# W050X.net
KiCad netlist of a schematic drawn in EAGLE
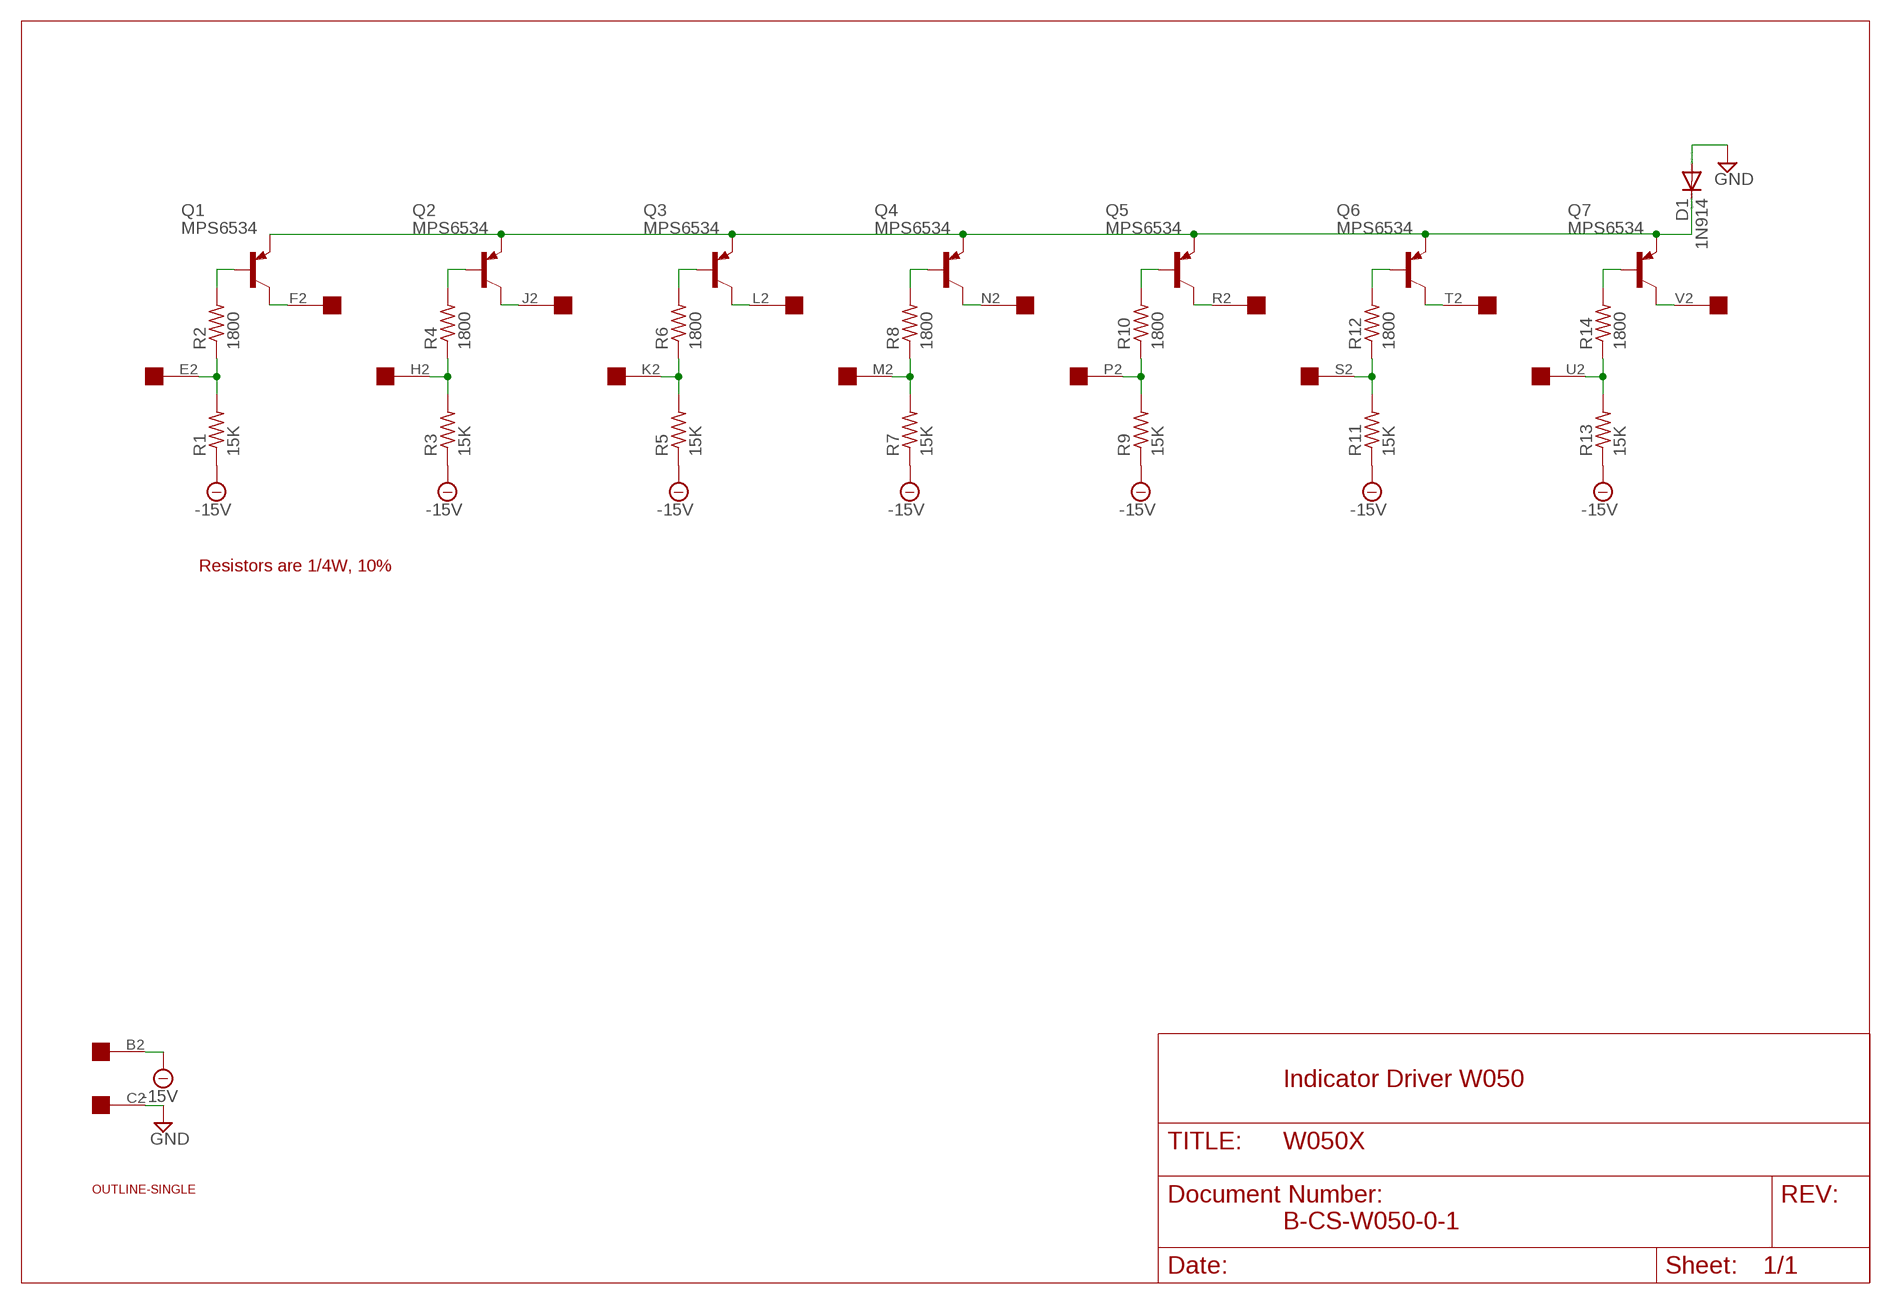
[diagram p0: schematic, sheet 1]

(export (version "E")
  (design (tool "Eeschema 10.0.6"))
  (components
    (comp (ref "D1")
      (value "1N914")
      (footprint "eagle-import:DO35-10")
      (libsource (lib "eagle-import") (part "1N4148DO35-10"))
    )
    (comp (ref "EDGE")
      (value "EDGE-1")
      (footprint "eagle-import:EDGE-CON1")
      (libsource (lib "eagle-import") (part "EDGE-1"))
    )
    (comp (ref "Q1")
      (value "MPS6534")
      (footprint "eagle-import:TO39")
      (libsource (lib "eagle-import") (part "2N2904"))
    )
    (comp (ref "Q2")
      (value "MPS6534")
      (footprint "eagle-import:TO39")
      (libsource (lib "eagle-import") (part "2N2904"))
    )
    (comp (ref "Q3")
      (value "MPS6534")
      (footprint "eagle-import:TO39")
      (libsource (lib "eagle-import") (part "2N2904"))
    )
    (comp (ref "Q4")
      (value "MPS6534")
      (footprint "eagle-import:TO39")
      (libsource (lib "eagle-import") (part "2N2904"))
    )
    (comp (ref "Q5")
      (value "MPS6534")
      (footprint "eagle-import:TO39")
      (libsource (lib "eagle-import") (part "2N2904"))
    )
    (comp (ref "Q6")
      (value "MPS6534")
      (footprint "eagle-import:TO39")
      (libsource (lib "eagle-import") (part "2N2904"))
    )
    (comp (ref "Q7")
      (value "MPS6534")
      (footprint "eagle-import:TO39")
      (libsource (lib "eagle-import") (part "2N2904"))
    )
    (comp (ref "R1")
      (value "15K")
      (footprint "eagle-import:0207_10")
      (libsource (lib "eagle-import") (part "R-US_0207/10"))
    )
    (comp (ref "R2")
      (value "1800")
      (footprint "eagle-import:0207_10")
      (libsource (lib "eagle-import") (part "R-US_0207/10"))
    )
    (comp (ref "R3")
      (value "15K")
      (footprint "eagle-import:0207_10")
      (libsource (lib "eagle-import") (part "R-US_0207/10"))
    )
    (comp (ref "R4")
      (value "1800")
      (footprint "eagle-import:0207_10")
      (libsource (lib "eagle-import") (part "R-US_0207/10"))
    )
    (comp (ref "R5")
      (value "15K")
      (footprint "eagle-import:0207_10")
      (libsource (lib "eagle-import") (part "R-US_0207/10"))
    )
    (comp (ref "R6")
      (value "1800")
      (footprint "eagle-import:0207_10")
      (libsource (lib "eagle-import") (part "R-US_0207/10"))
    )
    (comp (ref "R7")
      (value "15K")
      (footprint "eagle-import:0207_10")
      (libsource (lib "eagle-import") (part "R-US_0207/10"))
    )
    (comp (ref "R8")
      (value "1800")
      (footprint "eagle-import:0207_10")
      (libsource (lib "eagle-import") (part "R-US_0207/10"))
    )
    (comp (ref "R9")
      (value "15K")
      (footprint "eagle-import:0207_10")
      (libsource (lib "eagle-import") (part "R-US_0207/10"))
    )
    (comp (ref "R10")
      (value "1800")
      (footprint "eagle-import:0207_10")
      (libsource (lib "eagle-import") (part "R-US_0207/10"))
    )
    (comp (ref "R11")
      (value "15K")
      (footprint "eagle-import:0207_10")
      (libsource (lib "eagle-import") (part "R-US_0207/10"))
    )
    (comp (ref "R12")
      (value "1800")
      (footprint "eagle-import:0207_10")
      (libsource (lib "eagle-import") (part "R-US_0207/10"))
    )
    (comp (ref "R13")
      (value "15K")
      (footprint "eagle-import:0207_10")
      (libsource (lib "eagle-import") (part "R-US_0207/10"))
    )
    (comp (ref "R14")
      (value "1800")
      (footprint "eagle-import:0207_10")
      (libsource (lib "eagle-import") (part "R-US_0207/10"))
    )
    (comp (ref "U$1")
      (value "OUTLINE-SINGLE")
      (footprint "eagle-import:SINGLE")
      (libsource (lib "eagle-import") (part "OUTLINE-SINGLE"))
    )
  )
  (nets
    (net (code "1") (name "-15V") (class "Default")
      (node (ref "EDGE") (pin "B2") (pinfunction "1_B2") (pintype "bidirectional"))
      (node (ref "R1") (pin "1") (pinfunction "1_1") (pintype "passive"))
      (node (ref "R11") (pin "1") (pinfunction "1_1") (pintype "passive"))
      (node (ref "R13") (pin "1") (pinfunction "1_1") (pintype "passive"))
      (node (ref "R3") (pin "1") (pinfunction "1_1") (pintype "passive"))
      (node (ref "R5") (pin "1") (pinfunction "1_1") (pintype "passive"))
      (node (ref "R7") (pin "1") (pinfunction "1_1") (pintype "passive"))
      (node (ref "R9") (pin "1") (pinfunction "1_1") (pintype "passive"))
    )
    (net (code "2") (name "GND") (class "Default")
      (node (ref "D1") (pin "A") (pinfunction "A_A") (pintype "passive"))
      (node (ref "EDGE") (pin "C2") (pinfunction "1_C2") (pintype "bidirectional"))
    )
    (net (code "3") (name "Net-(EDGEE-1)") (class "Default")
      (node (ref "EDGE") (pin "E2") (pinfunction "1_E2") (pintype "bidirectional"))
      (node (ref "R1") (pin "2") (pinfunction "2_2") (pintype "passive"))
      (node (ref "R2") (pin "1") (pinfunction "1_1") (pintype "passive"))
    )
    (net (code "4") (name "Net-(EDGEF-1)") (class "Default")
      (node (ref "EDGE") (pin "F2") (pinfunction "1_F2") (pintype "bidirectional"))
      (node (ref "Q1") (pin "3") (pinfunction "C_3") (pintype "passive"))
    )
    (net (code "5") (name "Net-(EDGEG-1)") (class "Default")
      (node (ref "EDGE") (pin "H2") (pinfunction "1_H2") (pintype "bidirectional"))
      (node (ref "R3") (pin "2") (pinfunction "2_2") (pintype "passive"))
      (node (ref "R4") (pin "1") (pinfunction "1_1") (pintype "passive"))
    )
    (net (code "6") (name "Net-(EDGEH-1)") (class "Default")
      (node (ref "EDGE") (pin "J2") (pinfunction "1_J2") (pintype "bidirectional"))
      (node (ref "Q2") (pin "3") (pinfunction "C_3") (pintype "passive"))
    )
    (net (code "7") (name "Net-(EDGEI-1)") (class "Default")
      (node (ref "EDGE") (pin "K2") (pinfunction "1_K2") (pintype "bidirectional"))
      (node (ref "R5") (pin "2") (pinfunction "2_2") (pintype "passive"))
      (node (ref "R6") (pin "1") (pinfunction "1_1") (pintype "passive"))
    )
    (net (code "8") (name "Net-(EDGEJ-1)") (class "Default")
      (node (ref "EDGE") (pin "L2") (pinfunction "1_L2") (pintype "bidirectional"))
      (node (ref "Q3") (pin "3") (pinfunction "C_3") (pintype "passive"))
    )
    (net (code "9") (name "Net-(EDGEK-1)") (class "Default")
      (node (ref "EDGE") (pin "M2") (pinfunction "1_M2") (pintype "bidirectional"))
      (node (ref "R7") (pin "2") (pinfunction "2_2") (pintype "passive"))
      (node (ref "R8") (pin "1") (pinfunction "1_1") (pintype "passive"))
    )
    (net (code "10") (name "Net-(EDGEL-1)") (class "Default")
      (node (ref "EDGE") (pin "N2") (pinfunction "1_N2") (pintype "bidirectional"))
      (node (ref "Q4") (pin "3") (pinfunction "C_3") (pintype "passive"))
    )
    (net (code "11") (name "Net-(EDGEM-1)") (class "Default")
      (node (ref "EDGE") (pin "P2") (pinfunction "1_P2") (pintype "bidirectional"))
      (node (ref "R10") (pin "1") (pinfunction "1_1") (pintype "passive"))
      (node (ref "R9") (pin "2") (pinfunction "2_2") (pintype "passive"))
    )
    (net (code "12") (name "Net-(EDGEN-1)") (class "Default")
      (node (ref "EDGE") (pin "R2") (pinfunction "1_R2") (pintype "bidirectional"))
      (node (ref "Q5") (pin "3") (pinfunction "C_3") (pintype "passive"))
    )
    (net (code "13") (name "Net-(EDGEO-1)") (class "Default")
      (node (ref "EDGE") (pin "S2") (pinfunction "1_S2") (pintype "bidirectional"))
      (node (ref "R11") (pin "2") (pinfunction "2_2") (pintype "passive"))
      (node (ref "R12") (pin "1") (pinfunction "1_1") (pintype "passive"))
    )
    (net (code "14") (name "Net-(EDGEP-1)") (class "Default")
      (node (ref "EDGE") (pin "T2") (pinfunction "1_T2") (pintype "bidirectional"))
      (node (ref "Q6") (pin "3") (pinfunction "C_3") (pintype "passive"))
    )
    (net (code "15") (name "Net-(EDGEQ-1)") (class "Default")
      (node (ref "EDGE") (pin "U2") (pinfunction "1_U2") (pintype "bidirectional"))
      (node (ref "R13") (pin "2") (pinfunction "2_2") (pintype "passive"))
      (node (ref "R14") (pin "1") (pinfunction "1_1") (pintype "passive"))
    )
    (net (code "16") (name "Net-(EDGER-1)") (class "Default")
      (node (ref "EDGE") (pin "V2") (pinfunction "1_V2") (pintype "bidirectional"))
      (node (ref "Q7") (pin "3") (pinfunction "C_3") (pintype "passive"))
    )
    (net (code "17") (name "Net-(Q1-B)") (class "Default")
      (node (ref "Q1") (pin "2") (pinfunction "B_2") (pintype "passive"))
      (node (ref "R2") (pin "2") (pinfunction "2_2") (pintype "passive"))
    )
    (net (code "18") (name "Net-(Q1-E)") (class "Default")
      (node (ref "D1") (pin "C") (pinfunction "C_C") (pintype "passive"))
      (node (ref "Q1") (pin "1") (pinfunction "E_1") (pintype "passive"))
      (node (ref "Q2") (pin "1") (pinfunction "E_1") (pintype "passive"))
      (node (ref "Q3") (pin "1") (pinfunction "E_1") (pintype "passive"))
      (node (ref "Q4") (pin "1") (pinfunction "E_1") (pintype "passive"))
      (node (ref "Q5") (pin "1") (pinfunction "E_1") (pintype "passive"))
      (node (ref "Q6") (pin "1") (pinfunction "E_1") (pintype "passive"))
      (node (ref "Q7") (pin "1") (pinfunction "E_1") (pintype "passive"))
    )
    (net (code "19") (name "Net-(Q2-B)") (class "Default")
      (node (ref "Q2") (pin "2") (pinfunction "B_2") (pintype "passive"))
      (node (ref "R4") (pin "2") (pinfunction "2_2") (pintype "passive"))
    )
    (net (code "20") (name "Net-(Q3-B)") (class "Default")
      (node (ref "Q3") (pin "2") (pinfunction "B_2") (pintype "passive"))
      (node (ref "R6") (pin "2") (pinfunction "2_2") (pintype "passive"))
    )
    (net (code "21") (name "Net-(Q4-B)") (class "Default")
      (node (ref "Q4") (pin "2") (pinfunction "B_2") (pintype "passive"))
      (node (ref "R8") (pin "2") (pinfunction "2_2") (pintype "passive"))
    )
    (net (code "22") (name "Net-(Q5-B)") (class "Default")
      (node (ref "Q5") (pin "2") (pinfunction "B_2") (pintype "passive"))
      (node (ref "R10") (pin "2") (pinfunction "2_2") (pintype "passive"))
    )
    (net (code "23") (name "Net-(Q6-B)") (class "Default")
      (node (ref "Q6") (pin "2") (pinfunction "B_2") (pintype "passive"))
      (node (ref "R12") (pin "2") (pinfunction "2_2") (pintype "passive"))
    )
    (net (code "24") (name "Net-(Q7-B)") (class "Default")
      (node (ref "Q7") (pin "2") (pinfunction "B_2") (pintype "passive"))
      (node (ref "R14") (pin "2") (pinfunction "2_2") (pintype "passive"))
    )
  )
)
